# light_120mm_v1_0.net
KiCad netlist of a schematic drawn in EAGLE
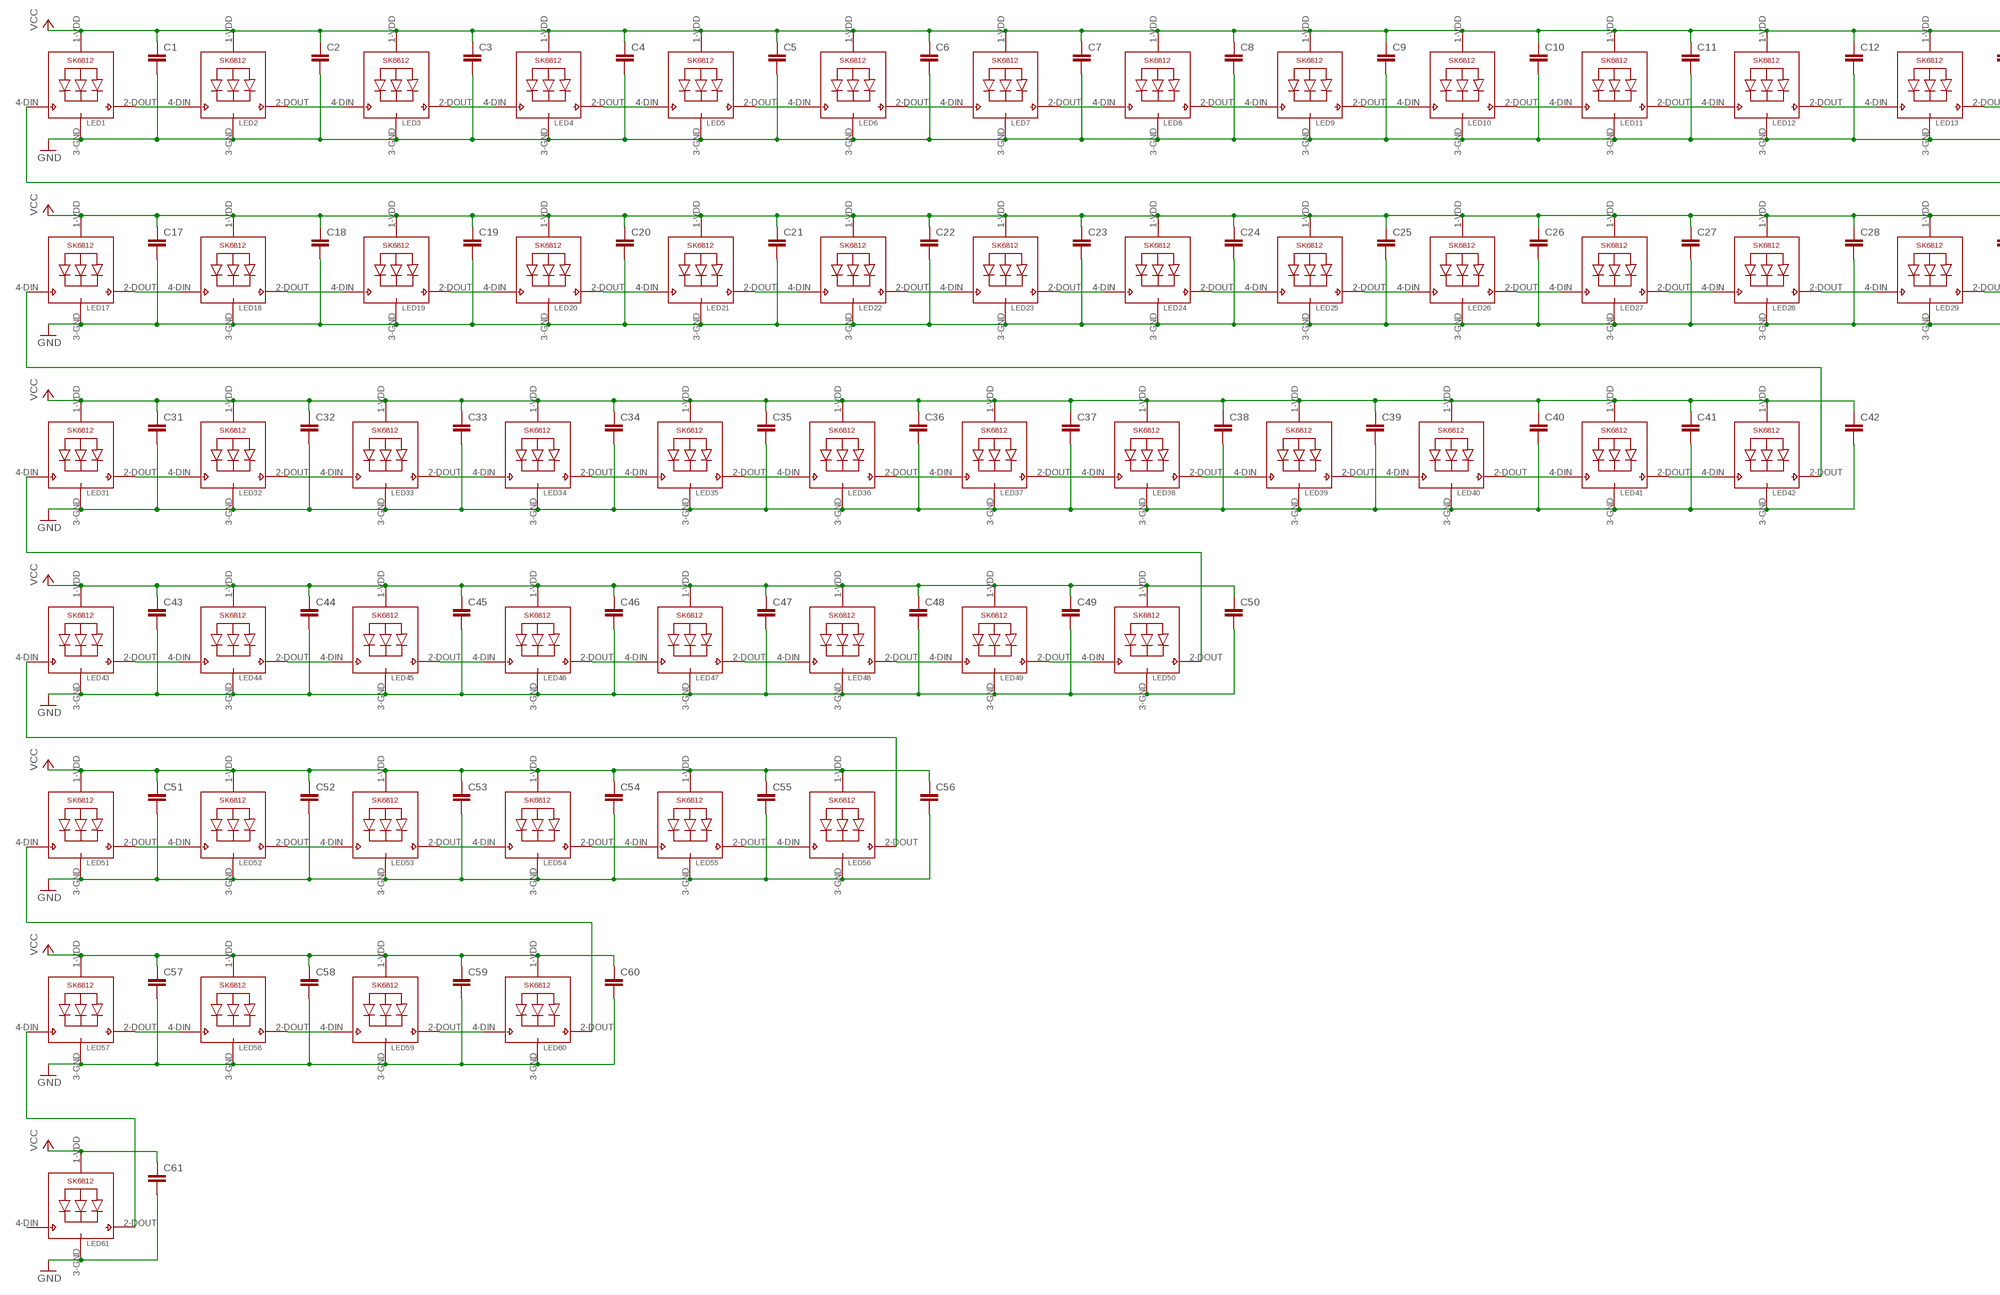
[diagram p0: schematic, sheet 1, part 1 of 2]
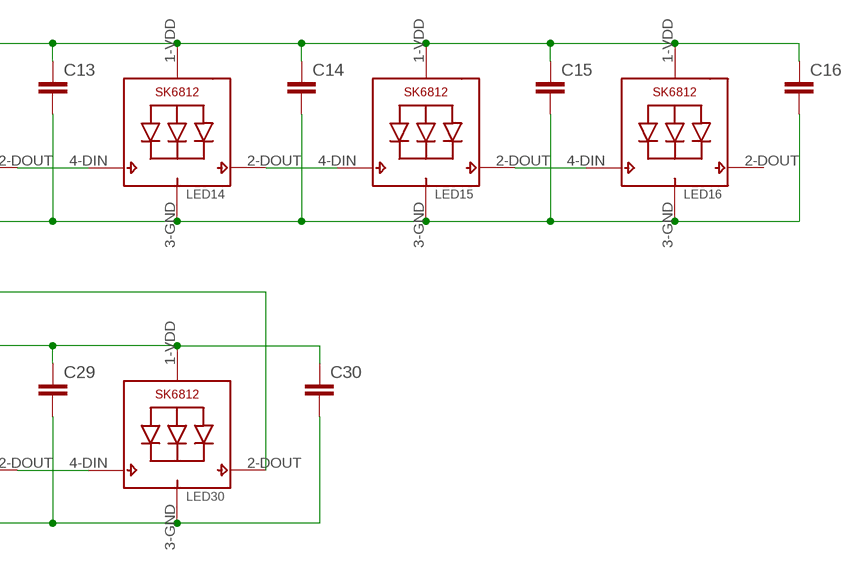
[diagram p1: schematic, sheet 1, part 2 of 2]

(export (version "E")
  (design (tool "Eeschema 10.0.6"))
  (components
    (comp (ref "C1")
      (value "C-EUC0805")
      (footprint "eagle-import:C0805")
      (libsource (lib "eagle-import") (part "C-EUC0805"))
    )
    (comp (ref "C2")
      (value "C-EUC0805")
      (footprint "eagle-import:C0805")
      (libsource (lib "eagle-import") (part "C-EUC0805"))
    )
    (comp (ref "C3")
      (value "C-EUC0805")
      (footprint "eagle-import:C0805")
      (libsource (lib "eagle-import") (part "C-EUC0805"))
    )
    (comp (ref "C4")
      (value "C-EUC0805")
      (footprint "eagle-import:C0805")
      (libsource (lib "eagle-import") (part "C-EUC0805"))
    )
    (comp (ref "C5")
      (value "C-EUC0805")
      (footprint "eagle-import:C0805")
      (libsource (lib "eagle-import") (part "C-EUC0805"))
    )
    (comp (ref "C6")
      (value "C-EUC0805")
      (footprint "eagle-import:C0805")
      (libsource (lib "eagle-import") (part "C-EUC0805"))
    )
    (comp (ref "C7")
      (value "C-EUC0805")
      (footprint "eagle-import:C0805")
      (libsource (lib "eagle-import") (part "C-EUC0805"))
    )
    (comp (ref "C8")
      (value "C-EUC0805")
      (footprint "eagle-import:C0805")
      (libsource (lib "eagle-import") (part "C-EUC0805"))
    )
    (comp (ref "C9")
      (value "C-EUC0805")
      (footprint "eagle-import:C0805")
      (libsource (lib "eagle-import") (part "C-EUC0805"))
    )
    (comp (ref "C10")
      (value "C-EUC0805")
      (footprint "eagle-import:C0805")
      (libsource (lib "eagle-import") (part "C-EUC0805"))
    )
    (comp (ref "C11")
      (value "C-EUC0805")
      (footprint "eagle-import:C0805")
      (libsource (lib "eagle-import") (part "C-EUC0805"))
    )
    (comp (ref "C12")
      (value "C-EUC0805")
      (footprint "eagle-import:C0805")
      (libsource (lib "eagle-import") (part "C-EUC0805"))
    )
    (comp (ref "C13")
      (value "C-EUC0805")
      (footprint "eagle-import:C0805")
      (libsource (lib "eagle-import") (part "C-EUC0805"))
    )
    (comp (ref "C14")
      (value "C-EUC0805")
      (footprint "eagle-import:C0805")
      (libsource (lib "eagle-import") (part "C-EUC0805"))
    )
    (comp (ref "C15")
      (value "C-EUC0805")
      (footprint "eagle-import:C0805")
      (libsource (lib "eagle-import") (part "C-EUC0805"))
    )
    (comp (ref "C16")
      (value "C-EUC0805")
      (footprint "eagle-import:C0805")
      (libsource (lib "eagle-import") (part "C-EUC0805"))
    )
    (comp (ref "C17")
      (value "C-EUC0805")
      (footprint "eagle-import:C0805")
      (libsource (lib "eagle-import") (part "C-EUC0805"))
    )
    (comp (ref "C18")
      (value "C-EUC0805")
      (footprint "eagle-import:C0805")
      (libsource (lib "eagle-import") (part "C-EUC0805"))
    )
    (comp (ref "C19")
      (value "C-EUC0805")
      (footprint "eagle-import:C0805")
      (libsource (lib "eagle-import") (part "C-EUC0805"))
    )
    (comp (ref "C20")
      (value "C-EUC0805")
      (footprint "eagle-import:C0805")
      (libsource (lib "eagle-import") (part "C-EUC0805"))
    )
    (comp (ref "C21")
      (value "C-EUC0805")
      (footprint "eagle-import:C0805")
      (libsource (lib "eagle-import") (part "C-EUC0805"))
    )
    (comp (ref "C22")
      (value "C-EUC0805")
      (footprint "eagle-import:C0805")
      (libsource (lib "eagle-import") (part "C-EUC0805"))
    )
    (comp (ref "C23")
      (value "C-EUC0805")
      (footprint "eagle-import:C0805")
      (libsource (lib "eagle-import") (part "C-EUC0805"))
    )
    (comp (ref "C24")
      (value "C-EUC0805")
      (footprint "eagle-import:C0805")
      (libsource (lib "eagle-import") (part "C-EUC0805"))
    )
    (comp (ref "C25")
      (value "C-EUC0805")
      (footprint "eagle-import:C0805")
      (libsource (lib "eagle-import") (part "C-EUC0805"))
    )
    (comp (ref "C26")
      (value "C-EUC0805")
      (footprint "eagle-import:C0805")
      (libsource (lib "eagle-import") (part "C-EUC0805"))
    )
    (comp (ref "C27")
      (value "C-EUC0805")
      (footprint "eagle-import:C0805")
      (libsource (lib "eagle-import") (part "C-EUC0805"))
    )
    (comp (ref "C28")
      (value "C-EUC0805")
      (footprint "eagle-import:C0805")
      (libsource (lib "eagle-import") (part "C-EUC0805"))
    )
    (comp (ref "C29")
      (value "C-EUC0805")
      (footprint "eagle-import:C0805")
      (libsource (lib "eagle-import") (part "C-EUC0805"))
    )
    (comp (ref "C30")
      (value "C-EUC0805")
      (footprint "eagle-import:C0805")
      (libsource (lib "eagle-import") (part "C-EUC0805"))
    )
    (comp (ref "C31")
      (value "C-EUC0805")
      (footprint "eagle-import:C0805")
      (libsource (lib "eagle-import") (part "C-EUC0805"))
    )
    (comp (ref "C32")
      (value "C-EUC0805")
      (footprint "eagle-import:C0805")
      (libsource (lib "eagle-import") (part "C-EUC0805"))
    )
    (comp (ref "C33")
      (value "C-EUC0805")
      (footprint "eagle-import:C0805")
      (libsource (lib "eagle-import") (part "C-EUC0805"))
    )
    (comp (ref "C34")
      (value "C-EUC0805")
      (footprint "eagle-import:C0805")
      (libsource (lib "eagle-import") (part "C-EUC0805"))
    )
    (comp (ref "C35")
      (value "C-EUC0805")
      (footprint "eagle-import:C0805")
      (libsource (lib "eagle-import") (part "C-EUC0805"))
    )
    (comp (ref "C36")
      (value "C-EUC0805")
      (footprint "eagle-import:C0805")
      (libsource (lib "eagle-import") (part "C-EUC0805"))
    )
    (comp (ref "C37")
      (value "C-EUC0805")
      (footprint "eagle-import:C0805")
      (libsource (lib "eagle-import") (part "C-EUC0805"))
    )
    (comp (ref "C38")
      (value "C-EUC0805")
      (footprint "eagle-import:C0805")
      (libsource (lib "eagle-import") (part "C-EUC0805"))
    )
    (comp (ref "C39")
      (value "C-EUC0805")
      (footprint "eagle-import:C0805")
      (libsource (lib "eagle-import") (part "C-EUC0805"))
    )
    (comp (ref "C40")
      (value "C-EUC0805")
      (footprint "eagle-import:C0805")
      (libsource (lib "eagle-import") (part "C-EUC0805"))
    )
    (comp (ref "C41")
      (value "C-EUC0805")
      (footprint "eagle-import:C0805")
      (libsource (lib "eagle-import") (part "C-EUC0805"))
    )
    (comp (ref "C42")
      (value "C-EUC0805")
      (footprint "eagle-import:C0805")
      (libsource (lib "eagle-import") (part "C-EUC0805"))
    )
    (comp (ref "C43")
      (value "C-EUC0805")
      (footprint "eagle-import:C0805")
      (libsource (lib "eagle-import") (part "C-EUC0805"))
    )
    (comp (ref "C44")
      (value "C-EUC0805")
      (footprint "eagle-import:C0805")
      (libsource (lib "eagle-import") (part "C-EUC0805"))
    )
    (comp (ref "C45")
      (value "C-EUC0805")
      (footprint "eagle-import:C0805")
      (libsource (lib "eagle-import") (part "C-EUC0805"))
    )
    (comp (ref "C46")
      (value "C-EUC0805")
      (footprint "eagle-import:C0805")
      (libsource (lib "eagle-import") (part "C-EUC0805"))
    )
    (comp (ref "C47")
      (value "C-EUC0805")
      (footprint "eagle-import:C0805")
      (libsource (lib "eagle-import") (part "C-EUC0805"))
    )
    (comp (ref "C48")
      (value "C-EUC0805")
      (footprint "eagle-import:C0805")
      (libsource (lib "eagle-import") (part "C-EUC0805"))
    )
    (comp (ref "C49")
      (value "C-EUC0805")
      (footprint "eagle-import:C0805")
      (libsource (lib "eagle-import") (part "C-EUC0805"))
    )
    (comp (ref "C50")
      (value "C-EUC0805")
      (footprint "eagle-import:C0805")
      (libsource (lib "eagle-import") (part "C-EUC0805"))
    )
    (comp (ref "C51")
      (value "C-EUC0805")
      (footprint "eagle-import:C0805")
      (libsource (lib "eagle-import") (part "C-EUC0805"))
    )
    (comp (ref "C52")
      (value "C-EUC0805")
      (footprint "eagle-import:C0805")
      (libsource (lib "eagle-import") (part "C-EUC0805"))
    )
    (comp (ref "C53")
      (value "C-EUC0805")
      (footprint "eagle-import:C0805")
      (libsource (lib "eagle-import") (part "C-EUC0805"))
    )
    (comp (ref "C54")
      (value "C-EUC0805")
      (footprint "eagle-import:C0805")
      (libsource (lib "eagle-import") (part "C-EUC0805"))
    )
    (comp (ref "C55")
      (value "C-EUC0805")
      (footprint "eagle-import:C0805")
      (libsource (lib "eagle-import") (part "C-EUC0805"))
    )
    (comp (ref "C56")
      (value "C-EUC0805")
      (footprint "eagle-import:C0805")
      (libsource (lib "eagle-import") (part "C-EUC0805"))
    )
    (comp (ref "C57")
      (value "C-EUC0805")
      (footprint "eagle-import:C0805")
      (libsource (lib "eagle-import") (part "C-EUC0805"))
    )
    (comp (ref "C58")
      (value "C-EUC0805")
      (footprint "eagle-import:C0805")
      (libsource (lib "eagle-import") (part "C-EUC0805"))
    )
    (comp (ref "C59")
      (value "C-EUC0805")
      (footprint "eagle-import:C0805")
      (libsource (lib "eagle-import") (part "C-EUC0805"))
    )
    (comp (ref "C60")
      (value "C-EUC0805")
      (footprint "eagle-import:C0805")
      (libsource (lib "eagle-import") (part "C-EUC0805"))
    )
    (comp (ref "C61")
      (value "C-EUC0805")
      (footprint "eagle-import:C0805")
      (libsource (lib "eagle-import") (part "C-EUC0805"))
    )
    (comp (ref "LED1")
      (value "SK6812_5050W")
      (footprint "eagle-import:LED5050_W")
      (libsource (lib "eagle-import") (part "SK6812_5050W"))
    )
    (comp (ref "LED2")
      (value "SK6812_5050W")
      (footprint "eagle-import:LED5050_W")
      (libsource (lib "eagle-import") (part "SK6812_5050W"))
    )
    (comp (ref "LED3")
      (value "SK6812_5050W")
      (footprint "eagle-import:LED5050_W")
      (libsource (lib "eagle-import") (part "SK6812_5050W"))
    )
    (comp (ref "LED4")
      (value "SK6812_5050W")
      (footprint "eagle-import:LED5050_W")
      (libsource (lib "eagle-import") (part "SK6812_5050W"))
    )
    (comp (ref "LED5")
      (value "SK6812_5050W")
      (footprint "eagle-import:LED5050_W")
      (libsource (lib "eagle-import") (part "SK6812_5050W"))
    )
    (comp (ref "LED6")
      (value "SK6812_5050W")
      (footprint "eagle-import:LED5050_W")
      (libsource (lib "eagle-import") (part "SK6812_5050W"))
    )
    (comp (ref "LED7")
      (value "SK6812_5050W")
      (footprint "eagle-import:LED5050_W")
      (libsource (lib "eagle-import") (part "SK6812_5050W"))
    )
    (comp (ref "LED8")
      (value "SK6812_5050W")
      (footprint "eagle-import:LED5050_W")
      (libsource (lib "eagle-import") (part "SK6812_5050W"))
    )
    (comp (ref "LED9")
      (value "SK6812_5050W")
      (footprint "eagle-import:LED5050_W")
      (libsource (lib "eagle-import") (part "SK6812_5050W"))
    )
    (comp (ref "LED10")
      (value "SK6812_5050W")
      (footprint "eagle-import:LED5050_W")
      (libsource (lib "eagle-import") (part "SK6812_5050W"))
    )
    (comp (ref "LED11")
      (value "SK6812_5050W")
      (footprint "eagle-import:LED5050_W")
      (libsource (lib "eagle-import") (part "SK6812_5050W"))
    )
    (comp (ref "LED12")
      (value "SK6812_5050W")
      (footprint "eagle-import:LED5050_W")
      (libsource (lib "eagle-import") (part "SK6812_5050W"))
    )
    (comp (ref "LED13")
      (value "SK6812_5050W")
      (footprint "eagle-import:LED5050_W")
      (libsource (lib "eagle-import") (part "SK6812_5050W"))
    )
    (comp (ref "LED14")
      (value "SK6812_5050W")
      (footprint "eagle-import:LED5050_W")
      (libsource (lib "eagle-import") (part "SK6812_5050W"))
    )
    (comp (ref "LED15")
      (value "SK6812_5050W")
      (footprint "eagle-import:LED5050_W")
      (libsource (lib "eagle-import") (part "SK6812_5050W"))
    )
    (comp (ref "LED16")
      (value "SK6812_5050W")
      (footprint "eagle-import:LED5050_W")
      (libsource (lib "eagle-import") (part "SK6812_5050W"))
    )
    (comp (ref "LED17")
      (value "SK6812_5050W")
      (footprint "eagle-import:LED5050_W")
      (libsource (lib "eagle-import") (part "SK6812_5050W"))
    )
    (comp (ref "LED18")
      (value "SK6812_5050W")
      (footprint "eagle-import:LED5050_W")
      (libsource (lib "eagle-import") (part "SK6812_5050W"))
    )
    (comp (ref "LED19")
      (value "SK6812_5050W")
      (footprint "eagle-import:LED5050_W")
      (libsource (lib "eagle-import") (part "SK6812_5050W"))
    )
    (comp (ref "LED20")
      (value "SK6812_5050W")
      (footprint "eagle-import:LED5050_W")
      (libsource (lib "eagle-import") (part "SK6812_5050W"))
    )
    (comp (ref "LED21")
      (value "SK6812_5050W")
      (footprint "eagle-import:LED5050_W")
      (libsource (lib "eagle-import") (part "SK6812_5050W"))
    )
    (comp (ref "LED22")
      (value "SK6812_5050W")
      (footprint "eagle-import:LED5050_W")
      (libsource (lib "eagle-import") (part "SK6812_5050W"))
    )
    (comp (ref "LED23")
      (value "SK6812_5050W")
      (footprint "eagle-import:LED5050_W")
      (libsource (lib "eagle-import") (part "SK6812_5050W"))
    )
    (comp (ref "LED24")
      (value "SK6812_5050W")
      (footprint "eagle-import:LED5050_W")
      (libsource (lib "eagle-import") (part "SK6812_5050W"))
    )
    (comp (ref "LED25")
      (value "SK6812_5050W")
      (footprint "eagle-import:LED5050_W")
      (libsource (lib "eagle-import") (part "SK6812_5050W"))
    )
    (comp (ref "LED26")
      (value "SK6812_5050W")
      (footprint "eagle-import:LED5050_W")
      (libsource (lib "eagle-import") (part "SK6812_5050W"))
    )
    (comp (ref "LED27")
      (value "SK6812_5050W")
      (footprint "eagle-import:LED5050_W")
      (libsource (lib "eagle-import") (part "SK6812_5050W"))
    )
    (comp (ref "LED28")
      (value "SK6812_5050W")
      (footprint "eagle-import:LED5050_W")
      (libsource (lib "eagle-import") (part "SK6812_5050W"))
    )
    (comp (ref "LED29")
      (value "SK6812_5050W")
      (footprint "eagle-import:LED5050_W")
      (libsource (lib "eagle-import") (part "SK6812_5050W"))
    )
    (comp (ref "LED30")
      (value "SK6812_5050W")
      (footprint "eagle-import:LED5050_W")
      (libsource (lib "eagle-import") (part "SK6812_5050W"))
    )
    (comp (ref "LED31")
      (value "SK6812_5050W")
      (footprint "eagle-import:LED5050_W")
      (libsource (lib "eagle-import") (part "SK6812_5050W"))
    )
    (comp (ref "LED32")
      (value "SK6812_5050W")
      (footprint "eagle-import:LED5050_W")
      (libsource (lib "eagle-import") (part "SK6812_5050W"))
    )
    (comp (ref "LED33")
      (value "SK6812_5050W")
      (footprint "eagle-import:LED5050_W")
      (libsource (lib "eagle-import") (part "SK6812_5050W"))
    )
    (comp (ref "LED34")
      (value "SK6812_5050W")
      (footprint "eagle-import:LED5050_W")
      (libsource (lib "eagle-import") (part "SK6812_5050W"))
    )
    (comp (ref "LED35")
      (value "SK6812_5050W")
      (footprint "eagle-import:LED5050_W")
      (libsource (lib "eagle-import") (part "SK6812_5050W"))
    )
    (comp (ref "LED36")
      (value "SK6812_5050W")
      (footprint "eagle-import:LED5050_W")
      (libsource (lib "eagle-import") (part "SK6812_5050W"))
    )
    (comp (ref "LED37")
      (value "SK6812_5050W")
      (footprint "eagle-import:LED5050_W")
      (libsource (lib "eagle-import") (part "SK6812_5050W"))
    )
    (comp (ref "LED38")
      (value "SK6812_5050W")
      (footprint "eagle-import:LED5050_W")
      (libsource (lib "eagle-import") (part "SK6812_5050W"))
    )
    (comp (ref "LED39")
      (value "SK6812_5050W")
      (footprint "eagle-import:LED5050_W")
      (libsource (lib "eagle-import") (part "SK6812_5050W"))
    )
    (comp (ref "LED40")
      (value "SK6812_5050W")
      (footprint "eagle-import:LED5050_W")
      (libsource (lib "eagle-import") (part "SK6812_5050W"))
    )
    (comp (ref "LED41")
      (value "SK6812_5050W")
      (footprint "eagle-import:LED5050_W")
      (libsource (lib "eagle-import") (part "SK6812_5050W"))
    )
    (comp (ref "LED42")
      (value "SK6812_5050W")
      (footprint "eagle-import:LED5050_W")
      (libsource (lib "eagle-import") (part "SK6812_5050W"))
    )
    (comp (ref "LED43")
      (value "SK6812_5050W")
      (footprint "eagle-import:LED5050_W")
      (libsource (lib "eagle-import") (part "SK6812_5050W"))
    )
    (comp (ref "LED44")
      (value "SK6812_5050W")
      (footprint "eagle-import:LED5050_W")
      (libsource (lib "eagle-import") (part "SK6812_5050W"))
    )
    (comp (ref "LED45")
      (value "SK6812_5050W")
      (footprint "eagle-import:LED5050_W")
      (libsource (lib "eagle-import") (part "SK6812_5050W"))
    )
    (comp (ref "LED46")
      (value "SK6812_5050W")
      (footprint "eagle-import:LED5050_W")
      (libsource (lib "eagle-import") (part "SK6812_5050W"))
    )
    (comp (ref "LED47")
      (value "SK6812_5050W")
      (footprint "eagle-import:LED5050_W")
      (libsource (lib "eagle-import") (part "SK6812_5050W"))
    )
    (comp (ref "LED48")
      (value "SK6812_5050W")
      (footprint "eagle-import:LED5050_W")
      (libsource (lib "eagle-import") (part "SK6812_5050W"))
    )
    (comp (ref "LED49")
      (value "SK6812_5050W")
      (footprint "eagle-import:LED5050_W")
      (libsource (lib "eagle-import") (part "SK6812_5050W"))
    )
    (comp (ref "LED50")
      (value "SK6812_5050W")
      (footprint "eagle-import:LED5050_W")
      (libsource (lib "eagle-import") (part "SK6812_5050W"))
    )
    (comp (ref "LED51")
      (value "SK6812_5050W")
      (footprint "eagle-import:LED5050_W")
      (libsource (lib "eagle-import") (part "SK6812_5050W"))
    )
    (comp (ref "LED52")
      (value "SK6812_5050W")
      (footprint "eagle-import:LED5050_W")
      (libsource (lib "eagle-import") (part "SK6812_5050W"))
    )
    (comp (ref "LED53")
      (value "SK6812_5050W")
      (footprint "eagle-import:LED5050_W")
      (libsource (lib "eagle-import") (part "SK6812_5050W"))
    )
    (comp (ref "LED54")
      (value "SK6812_5050W")
      (footprint "eagle-import:LED5050_W")
      (libsource (lib "eagle-import") (part "SK6812_5050W"))
    )
    (comp (ref "LED55")
      (value "SK6812_5050W")
      (footprint "eagle-import:LED5050_W")
      (libsource (lib "eagle-import") (part "SK6812_5050W"))
    )
    (comp (ref "LED56")
      (value "SK6812_5050W")
      (footprint "eagle-import:LED5050_W")
      (libsource (lib "eagle-import") (part "SK6812_5050W"))
    )
    (comp (ref "LED57")
      (value "SK6812_5050W")
      (footprint "eagle-import:LED5050_W")
      (libsource (lib "eagle-import") (part "SK6812_5050W"))
    )
    (comp (ref "LED58")
      (value "SK6812_5050W")
      (footprint "eagle-import:LED5050_W")
      (libsource (lib "eagle-import") (part "SK6812_5050W"))
    )
    (comp (ref "LED59")
      (value "SK6812_5050W")
      (footprint "eagle-import:LED5050_W")
      (libsource (lib "eagle-import") (part "SK6812_5050W"))
    )
    (comp (ref "LED60")
      (value "SK6812_5050W")
      (footprint "eagle-import:LED5050_W")
      (libsource (lib "eagle-import") (part "SK6812_5050W"))
    )
    (comp (ref "LED61")
      (value "SK6812_5050W")
      (footprint "eagle-import:LED5050_W")
      (libsource (lib "eagle-import") (part "SK6812_5050W"))
    )
  )
  (nets
    (net (code "1") (name "GND") (class "Default")
      (node (ref "C1") (pin "2") (pinfunction "2_2") (pintype "passive"))
      (node (ref "C10") (pin "2") (pinfunction "2_2") (pintype "passive"))
      (node (ref "C11") (pin "2") (pinfunction "2_2") (pintype "passive"))
      (node (ref "C12") (pin "2") (pinfunction "2_2") (pintype "passive"))
      (node (ref "C13") (pin "2") (pinfunction "2_2") (pintype "passive"))
      (node (ref "C14") (pin "2") (pinfunction "2_2") (pintype "passive"))
      (node (ref "C15") (pin "2") (pinfunction "2_2") (pintype "passive"))
      (node (ref "C16") (pin "2") (pinfunction "2_2") (pintype "passive"))
      (node (ref "C17") (pin "2") (pinfunction "2_2") (pintype "passive"))
      (node (ref "C18") (pin "2") (pinfunction "2_2") (pintype "passive"))
      (node (ref "C19") (pin "2") (pinfunction "2_2") (pintype "passive"))
      (node (ref "C2") (pin "2") (pinfunction "2_2") (pintype "passive"))
      (node (ref "C20") (pin "2") (pinfunction "2_2") (pintype "passive"))
      (node (ref "C21") (pin "2") (pinfunction "2_2") (pintype "passive"))
      (node (ref "C22") (pin "2") (pinfunction "2_2") (pintype "passive"))
      (node (ref "C23") (pin "2") (pinfunction "2_2") (pintype "passive"))
      (node (ref "C24") (pin "2") (pinfunction "2_2") (pintype "passive"))
      (node (ref "C25") (pin "2") (pinfunction "2_2") (pintype "passive"))
      (node (ref "C26") (pin "2") (pinfunction "2_2") (pintype "passive"))
      (node (ref "C27") (pin "2") (pinfunction "2_2") (pintype "passive"))
      (node (ref "C28") (pin "2") (pinfunction "2_2") (pintype "passive"))
      (node (ref "C29") (pin "2") (pinfunction "2_2") (pintype "passive"))
      (node (ref "C3") (pin "2") (pinfunction "2_2") (pintype "passive"))
      (node (ref "C30") (pin "2") (pinfunction "2_2") (pintype "passive"))
      (node (ref "C31") (pin "2") (pinfunction "2_2") (pintype "passive"))
      (node (ref "C32") (pin "2") (pinfunction "2_2") (pintype "passive"))
      (node (ref "C33") (pin "2") (pinfunction "2_2") (pintype "passive"))
      (node (ref "C34") (pin "2") (pinfunction "2_2") (pintype "passive"))
      (node (ref "C35") (pin "2") (pinfunction "2_2") (pintype "passive"))
      (node (ref "C36") (pin "2") (pinfunction "2_2") (pintype "passive"))
      (node (ref "C37") (pin "2") (pinfunction "2_2") (pintype "passive"))
      (node (ref "C38") (pin "2") (pinfunction "2_2") (pintype "passive"))
      (node (ref "C39") (pin "2") (pinfunction "2_2") (pintype "passive"))
      (node (ref "C4") (pin "2") (pinfunction "2_2") (pintype "passive"))
      (node (ref "C40") (pin "2") (pinfunction "2_2") (pintype "passive"))
      (node (ref "C41") (pin "2") (pinfunction "2_2") (pintype "passive"))
      (node (ref "C42") (pin "2") (pinfunction "2_2") (pintype "passive"))
      (node (ref "C43") (pin "2") (pinfunction "2_2") (pintype "passive"))
      (node (ref "C44") (pin "2") (pinfunction "2_2") (pintype "passive"))
      (node (ref "C45") (pin "2") (pinfunction "2_2") (pintype "passive"))
      (node (ref "C46") (pin "2") (pinfunction "2_2") (pintype "passive"))
      (node (ref "C47") (pin "2") (pinfunction "2_2") (pintype "passive"))
      (node (ref "C48") (pin "2") (pinfunction "2_2") (pintype "passive"))
      (node (ref "C49") (pin "2") (pinfunction "2_2") (pintype "passive"))
      (node (ref "C5") (pin "2") (pinfunction "2_2") (pintype "passive"))
      (node (ref "C50") (pin "2") (pinfunction "2_2") (pintype "passive"))
      (node (ref "C51") (pin "2") (pinfunction "2_2") (pintype "passive"))
      (node (ref "C52") (pin "2") (pinfunction "2_2") (pintype "passive"))
      (node (ref "C53") (pin "2") (pinfunction "2_2") (pintype "passive"))
      (node (ref "C54") (pin "2") (pinfunction "2_2") (pintype "passive"))
      (node (ref "C55") (pin "2") (pinfunction "2_2") (pintype "passive"))
      (node (ref "C56") (pin "2") (pinfunction "2_2") (pintype "passive"))
      (node (ref "C57") (pin "2") (pinfunction "2_2") (pintype "passive"))
      (node (ref "C58") (pin "2") (pinfunction "2_2") (pintype "passive"))
      (node (ref "C59") (pin "2") (pinfunction "2_2") (pintype "passive"))
      (node (ref "C6") (pin "2") (pinfunction "2_2") (pintype "passive"))
      (node (ref "C60") (pin "2") (pinfunction "2_2") (pintype "passive"))
      (node (ref "C61") (pin "2") (pinfunction "2_2") (pintype "passive"))
      (node (ref "C7") (pin "2") (pinfunction "2_2") (pintype "passive"))
      (node (ref "C8") (pin "2") (pinfunction "2_2") (pintype "passive"))
      (node (ref "C9") (pin "2") (pinfunction "2_2") (pintype "passive"))
      (node (ref "LED1") (pin "3-GND") (pinfunction "GND_3-GND") (pintype "power_in"))
      (node (ref "LED10") (pin "3-GND") (pinfunction "GND_3-GND") (pintype "power_in"))
      (node (ref "LED11") (pin "3-GND") (pinfunction "GND_3-GND") (pintype "power_in"))
      (node (ref "LED12") (pin "3-GND") (pinfunction "GND_3-GND") (pintype "power_in"))
      (node (ref "LED13") (pin "3-GND") (pinfunction "GND_3-GND") (pintype "power_in"))
      (node (ref "LED14") (pin "3-GND") (pinfunction "GND_3-GND") (pintype "power_in"))
      (node (ref "LED15") (pin "3-GND") (pinfunction "GND_3-GND") (pintype "power_in"))
      (node (ref "LED16") (pin "3-GND") (pinfunction "GND_3-GND") (pintype "power_in"))
      (node (ref "LED17") (pin "3-GND") (pinfunction "GND_3-GND") (pintype "power_in"))
      (node (ref "LED18") (pin "3-GND") (pinfunction "GND_3-GND") (pintype "power_in"))
      (node (ref "LED19") (pin "3-GND") (pinfunction "GND_3-GND") (pintype "power_in"))
      (node (ref "LED2") (pin "3-GND") (pinfunction "GND_3-GND") (pintype "power_in"))
      (node (ref "LED20") (pin "3-GND") (pinfunction "GND_3-GND") (pintype "power_in"))
      (node (ref "LED21") (pin "3-GND") (pinfunction "GND_3-GND") (pintype "power_in"))
      (node (ref "LED22") (pin "3-GND") (pinfunction "GND_3-GND") (pintype "power_in"))
      (node (ref "LED23") (pin "3-GND") (pinfunction "GND_3-GND") (pintype "power_in"))
      (node (ref "LED24") (pin "3-GND") (pinfunction "GND_3-GND") (pintype "power_in"))
      (node (ref "LED25") (pin "3-GND") (pinfunction "GND_3-GND") (pintype "power_in"))
      (node (ref "LED26") (pin "3-GND") (pinfunction "GND_3-GND") (pintype "power_in"))
      (node (ref "LED27") (pin "3-GND") (pinfunction "GND_3-GND") (pintype "power_in"))
      (node (ref "LED28") (pin "3-GND") (pinfunction "GND_3-GND") (pintype "power_in"))
      (node (ref "LED29") (pin "3-GND") (pinfunction "GND_3-GND") (pintype "power_in"))
      (node (ref "LED3") (pin "3-GND") (pinfunction "GND_3-GND") (pintype "power_in"))
      (node (ref "LED30") (pin "3-GND") (pinfunction "GND_3-GND") (pintype "power_in"))
      (node (ref "LED31") (pin "3-GND") (pinfunction "GND_3-GND") (pintype "power_in"))
      (node (ref "LED32") (pin "3-GND") (pinfunction "GND_3-GND") (pintype "power_in"))
      (node (ref "LED33") (pin "3-GND") (pinfunction "GND_3-GND") (pintype "power_in"))
      (node (ref "LED34") (pin "3-GND") (pinfunction "GND_3-GND") (pintype "power_in"))
      (node (ref "LED35") (pin "3-GND") (pinfunction "GND_3-GND") (pintype "power_in"))
      (node (ref "LED36") (pin "3-GND") (pinfunction "GND_3-GND") (pintype "power_in"))
      (node (ref "LED37") (pin "3-GND") (pinfunction "GND_3-GND") (pintype "power_in"))
      (node (ref "LED38") (pin "3-GND") (pinfunction "GND_3-GND") (pintype "power_in"))
      (node (ref "LED39") (pin "3-GND") (pinfunction "GND_3-GND") (pintype "power_in"))
      (node (ref "LED4") (pin "3-GND") (pinfunction "GND_3-GND") (pintype "power_in"))
      (node (ref "LED40") (pin "3-GND") (pinfunction "GND_3-GND") (pintype "power_in"))
      (node (ref "LED41") (pin "3-GND") (pinfunction "GND_3-GND") (pintype "power_in"))
      (node (ref "LED42") (pin "3-GND") (pinfunction "GND_3-GND") (pintype "power_in"))
      (node (ref "LED43") (pin "3-GND") (pinfunction "GND_3-GND") (pintype "power_in"))
      (node (ref "LED44") (pin "3-GND") (pinfunction "GND_3-GND") (pintype "power_in"))
      (node (ref "LED45") (pin "3-GND") (pinfunction "GND_3-GND") (pintype "power_in"))
      (node (ref "LED46") (pin "3-GND") (pinfunction "GND_3-GND") (pintype "power_in"))
      (node (ref "LED47") (pin "3-GND") (pinfunction "GND_3-GND") (pintype "power_in"))
      (node (ref "LED48") (pin "3-GND") (pinfunction "GND_3-GND") (pintype "power_in"))
      (node (ref "LED49") (pin "3-GND") (pinfunction "GND_3-GND") (pintype "power_in"))
      (node (ref "LED5") (pin "3-GND") (pinfunction "GND_3-GND") (pintype "power_in"))
      (node (ref "LED50") (pin "3-GND") (pinfunction "GND_3-GND") (pintype "power_in"))
      (node (ref "LED51") (pin "3-GND") (pinfunction "GND_3-GND") (pintype "power_in"))
      (node (ref "LED52") (pin "3-GND") (pinfunction "GND_3-GND") (pintype "power_in"))
      (node (ref "LED53") (pin "3-GND") (pinfunction "GND_3-GND") (pintype "power_in"))
      (node (ref "LED54") (pin "3-GND") (pinfunction "GND_3-GND") (pintype "power_in"))
      (node (ref "LED55") (pin "3-GND") (pinfunction "GND_3-GND") (pintype "power_in"))
      (node (ref "LED56") (pin "3-GND") (pinfunction "GND_3-GND") (pintype "power_in"))
      (node (ref "LED57") (pin "3-GND") (pinfunction "GND_3-GND") (pintype "power_in"))
      (node (ref "LED58") (pin "3-GND") (pinfunction "GND_3-GND") (pintype "power_in"))
      (node (ref "LED59") (pin "3-GND") (pinfunction "GND_3-GND") (pintype "power_in"))
      (node (ref "LED6") (pin "3-GND") (pinfunction "GND_3-GND") (pintype "power_in"))
      (node (ref "LED60") (pin "3-GND") (pinfunction "GND_3-GND") (pintype "power_in"))
      (node (ref "LED61") (pin "3-GND") (pinfunction "GND_3-GND") (pintype "power_in"))
      (node (ref "LED7") (pin "3-GND") (pinfunction "GND_3-GND") (pintype "power_in"))
      (node (ref "LED8") (pin "3-GND") (pinfunction "GND_3-GND") (pintype "power_in"))
      (node (ref "LED9") (pin "3-GND") (pinfunction "GND_3-GND") (pintype "power_in"))
    )
    (net (code "2") (name "Net-(LED1-DI)") (class "Default")
      (node (ref "LED1") (pin "4-DIN") (pinfunction "DI_4-DIN") (pintype "input"))
      (node (ref "LED30") (pin "2-DOUT") (pinfunction "DO_2-DOUT") (pintype "output"))
    )
    (net (code "3") (name "Net-(LED1-DO)") (class "Default")
      (node (ref "LED1") (pin "2-DOUT") (pinfunction "DO_2-DOUT") (pintype "output"))
      (node (ref "LED2") (pin "4-DIN") (pinfunction "DI_4-DIN") (pintype "input"))
    )
    (net (code "4") (name "Net-(LED2-DO)") (class "Default")
      (node (ref "LED2") (pin "2-DOUT") (pinfunction "DO_2-DOUT") (pintype "output"))
      (node (ref "LED3") (pin "4-DIN") (pinfunction "DI_4-DIN") (pintype "input"))
    )
    (net (code "5") (name "Net-(LED3-DO)") (class "Default")
      (node (ref "LED3") (pin "2-DOUT") (pinfunction "DO_2-DOUT") (pintype "output"))
      (node (ref "LED4") (pin "4-DIN") (pinfunction "DI_4-DIN") (pintype "input"))
    )
    (net (code "6") (name "Net-(LED4-DO)") (class "Default")
      (node (ref "LED4") (pin "2-DOUT") (pinfunction "DO_2-DOUT") (pintype "output"))
      (node (ref "LED5") (pin "4-DIN") (pinfunction "DI_4-DIN") (pintype "input"))
    )
    (net (code "7") (name "Net-(LED5-DO)") (class "Default")
      (node (ref "LED5") (pin "2-DOUT") (pinfunction "DO_2-DOUT") (pintype "output"))
      (node (ref "LED6") (pin "4-DIN") (pinfunction "DI_4-DIN") (pintype "input"))
    )
    (net (code "8") (name "Net-(LED6-DO)") (class "Default")
      (node (ref "LED6") (pin "2-DOUT") (pinfunction "DO_2-DOUT") (pintype "output"))
      (node (ref "LED7") (pin "4-DIN") (pinfunction "DI_4-DIN") (pintype "input"))
    )
    (net (code "9") (name "Net-(LED7-DO)") (class "Default")
      (node (ref "LED7") (pin "2-DOUT") (pinfunction "DO_2-DOUT") (pintype "output"))
      (node (ref "LED8") (pin "4-DIN") (pinfunction "DI_4-DIN") (pintype "input"))
    )
    (net (code "10") (name "Net-(LED8-DO)") (class "Default")
      (node (ref "LED8") (pin "2-DOUT") (pinfunction "DO_2-DOUT") (pintype "output"))
      (node (ref "LED9") (pin "4-DIN") (pinfunction "DI_4-DIN") (pintype "input"))
    )
    (net (code "11") (name "Net-(LED10-DI)") (class "Default")
      (node (ref "LED10") (pin "4-DIN") (pinfunction "DI_4-DIN") (pintype "input"))
      (node (ref "LED9") (pin "2-DOUT") (pinfunction "DO_2-DOUT") (pintype "output"))
    )
    (net (code "12") (name "Net-(LED10-DO)") (class "Default")
      (node (ref "LED10") (pin "2-DOUT") (pinfunction "DO_2-DOUT") (pintype "output"))
      (node (ref "LED11") (pin "4-DIN") (pinfunction "DI_4-DIN") (pintype "input"))
    )
    (net (code "13") (name "Net-(LED11-DO)") (class "Default")
      (node (ref "LED11") (pin "2-DOUT") (pinfunction "DO_2-DOUT") (pintype "output"))
      (node (ref "LED12") (pin "4-DIN") (pinfunction "DI_4-DIN") (pintype "input"))
    )
    (net (code "14") (name "Net-(LED12-DO)") (class "Default")
      (node (ref "LED12") (pin "2-DOUT") (pinfunction "DO_2-DOUT") (pintype "output"))
      (node (ref "LED13") (pin "4-DIN") (pinfunction "DI_4-DIN") (pintype "input"))
    )
    (net (code "15") (name "Net-(LED13-DO)") (class "Default")
      (node (ref "LED13") (pin "2-DOUT") (pinfunction "DO_2-DOUT") (pintype "output"))
      (node (ref "LED14") (pin "4-DIN") (pinfunction "DI_4-DIN") (pintype "input"))
    )
    (net (code "16") (name "Net-(LED14-DO)") (class "Default")
      (node (ref "LED14") (pin "2-DOUT") (pinfunction "DO_2-DOUT") (pintype "output"))
      (node (ref "LED15") (pin "4-DIN") (pinfunction "DI_4-DIN") (pintype "input"))
    )
    (net (code "17") (name "Net-(LED15-DO)") (class "Default")
      (node (ref "LED15") (pin "2-DOUT") (pinfunction "DO_2-DOUT") (pintype "output"))
      (node (ref "LED16") (pin "4-DIN") (pinfunction "DI_4-DIN") (pintype "input"))
    )
    (net (code "18") (name "Net-(LED17-DI)") (class "Default")
      (node (ref "LED17") (pin "4-DIN") (pinfunction "DI_4-DIN") (pintype "input"))
      (node (ref "LED42") (pin "2-DOUT") (pinfunction "DO_2-DOUT") (pintype "output"))
    )
    (net (code "19") (name "Net-(LED17-DO)") (class "Default")
      (node (ref "LED17") (pin "2-DOUT") (pinfunction "DO_2-DOUT") (pintype "output"))
      (node (ref "LED18") (pin "4-DIN") (pinfunction "DI_4-DIN") (pintype "input"))
    )
    (net (code "20") (name "Net-(LED18-DO)") (class "Default")
      (node (ref "LED18") (pin "2-DOUT") (pinfunction "DO_2-DOUT") (pintype "output"))
      (node (ref "LED19") (pin "4-DIN") (pinfunction "DI_4-DIN") (pintype "input"))
    )
    (net (code "21") (name "Net-(LED19-DO)") (class "Default")
      (node (ref "LED19") (pin "2-DOUT") (pinfunction "DO_2-DOUT") (pintype "output"))
      (node (ref "LED20") (pin "4-DIN") (pinfunction "DI_4-DIN") (pintype "input"))
    )
    (net (code "22") (name "Net-(LED20-DO)") (class "Default")
      (node (ref "LED20") (pin "2-DOUT") (pinfunction "DO_2-DOUT") (pintype "output"))
      (node (ref "LED21") (pin "4-DIN") (pinfunction "DI_4-DIN") (pintype "input"))
    )
    (net (code "23") (name "Net-(LED21-DO)") (class "Default")
      (node (ref "LED21") (pin "2-DOUT") (pinfunction "DO_2-DOUT") (pintype "output"))
      (node (ref "LED22") (pin "4-DIN") (pinfunction "DI_4-DIN") (pintype "input"))
    )
    (net (code "24") (name "Net-(LED22-DO)") (class "Default")
      (node (ref "LED22") (pin "2-DOUT") (pinfunction "DO_2-DOUT") (pintype "output"))
      (node (ref "LED23") (pin "4-DIN") (pinfunction "DI_4-DIN") (pintype "input"))
    )
    (net (code "25") (name "Net-(LED23-DO)") (class "Default")
      (node (ref "LED23") (pin "2-DOUT") (pinfunction "DO_2-DOUT") (pintype "output"))
      (node (ref "LED24") (pin "4-DIN") (pinfunction "DI_4-DIN") (pintype "input"))
    )
    (net (code "26") (name "Net-(LED24-DO)") (class "Default")
      (node (ref "LED24") (pin "2-DOUT") (pinfunction "DO_2-DOUT") (pintype "output"))
      (node (ref "LED25") (pin "4-DIN") (pinfunction "DI_4-DIN") (pintype "input"))
    )
    (net (code "27") (name "Net-(LED25-DO)") (class "Default")
      (node (ref "LED25") (pin "2-DOUT") (pinfunction "DO_2-DOUT") (pintype "output"))
      (node (ref "LED26") (pin "4-DIN") (pinfunction "DI_4-DIN") (pintype "input"))
    )
    (net (code "28") (name "Net-(LED26-DO)") (class "Default")
      (node (ref "LED26") (pin "2-DOUT") (pinfunction "DO_2-DOUT") (pintype "output"))
      (node (ref "LED27") (pin "4-DIN") (pinfunction "DI_4-DIN") (pintype "input"))
    )
    (net (code "29") (name "Net-(LED27-DO)") (class "Default")
      (node (ref "LED27") (pin "2-DOUT") (pinfunction "DO_2-DOUT") (pintype "output"))
      (node (ref "LED28") (pin "4-DIN") (pinfunction "DI_4-DIN") (pintype "input"))
    )
    (net (code "30") (name "Net-(LED28-DO)") (class "Default")
      (node (ref "LED28") (pin "2-DOUT") (pinfunction "DO_2-DOUT") (pintype "output"))
      (node (ref "LED29") (pin "4-DIN") (pinfunction "DI_4-DIN") (pintype "input"))
    )
    (net (code "31") (name "Net-(LED29-DO)") (class "Default")
      (node (ref "LED29") (pin "2-DOUT") (pinfunction "DO_2-DOUT") (pintype "output"))
      (node (ref "LED30") (pin "4-DIN") (pinfunction "DI_4-DIN") (pintype "input"))
    )
    (net (code "32") (name "Net-(LED31-DI)") (class "Default")
      (node (ref "LED31") (pin "4-DIN") (pinfunction "DI_4-DIN") (pintype "input"))
      (node (ref "LED50") (pin "2-DOUT") (pinfunction "DO_2-DOUT") (pintype "output"))
    )
    (net (code "33") (name "Net-(LED31-DO)") (class "Default")
      (node (ref "LED31") (pin "2-DOUT") (pinfunction "DO_2-DOUT") (pintype "output"))
      (node (ref "LED32") (pin "4-DIN") (pinfunction "DI_4-DIN") (pintype "input"))
    )
    (net (code "34") (name "Net-(LED32-DO)") (class "Default")
      (node (ref "LED32") (pin "2-DOUT") (pinfunction "DO_2-DOUT") (pintype "output"))
      (node (ref "LED33") (pin "4-DIN") (pinfunction "DI_4-DIN") (pintype "input"))
    )
    (net (code "35") (name "Net-(LED33-DO)") (class "Default")
      (node (ref "LED33") (pin "2-DOUT") (pinfunction "DO_2-DOUT") (pintype "output"))
      (node (ref "LED34") (pin "4-DIN") (pinfunction "DI_4-DIN") (pintype "input"))
    )
    (net (code "36") (name "Net-(LED34-DO)") (class "Default")
      (node (ref "LED34") (pin "2-DOUT") (pinfunction "DO_2-DOUT") (pintype "output"))
      (node (ref "LED35") (pin "4-DIN") (pinfunction "DI_4-DIN") (pintype "input"))
    )
    (net (code "37") (name "Net-(LED35-DO)") (class "Default")
      (node (ref "LED35") (pin "2-DOUT") (pinfunction "DO_2-DOUT") (pintype "output"))
      (node (ref "LED36") (pin "4-DIN") (pinfunction "DI_4-DIN") (pintype "input"))
    )
    (net (code "38") (name "Net-(LED36-DO)") (class "Default")
      (node (ref "LED36") (pin "2-DOUT") (pinfunction "DO_2-DOUT") (pintype "output"))
      (node (ref "LED37") (pin "4-DIN") (pinfunction "DI_4-DIN") (pintype "input"))
    )
    (net (code "39") (name "Net-(LED37-DO)") (class "Default")
      (node (ref "LED37") (pin "2-DOUT") (pinfunction "DO_2-DOUT") (pintype "output"))
      (node (ref "LED38") (pin "4-DIN") (pinfunction "DI_4-DIN") (pintype "input"))
    )
    (net (code "40") (name "Net-(LED38-DO)") (class "Default")
      (node (ref "LED38") (pin "2-DOUT") (pinfunction "DO_2-DOUT") (pintype "output"))
      (node (ref "LED39") (pin "4-DIN") (pinfunction "DI_4-DIN") (pintype "input"))
    )
    (net (code "41") (name "Net-(LED39-DO)") (class "Default")
      (node (ref "LED39") (pin "2-DOUT") (pinfunction "DO_2-DOUT") (pintype "output"))
      (node (ref "LED40") (pin "4-DIN") (pinfunction "DI_4-DIN") (pintype "input"))
    )
    (net (code "42") (name "Net-(LED40-DO)") (class "Default")
      (node (ref "LED40") (pin "2-DOUT") (pinfunction "DO_2-DOUT") (pintype "output"))
      (node (ref "LED41") (pin "4-DIN") (pinfunction "DI_4-DIN") (pintype "input"))
    )
    (net (code "43") (name "Net-(LED41-DO)") (class "Default")
      (node (ref "LED41") (pin "2-DOUT") (pinfunction "DO_2-DOUT") (pintype "output"))
      (node (ref "LED42") (pin "4-DIN") (pinfunction "DI_4-DIN") (pintype "input"))
    )
    (net (code "44") (name "Net-(LED43-DI)") (class "Default")
      (node (ref "LED43") (pin "4-DIN") (pinfunction "DI_4-DIN") (pintype "input"))
      (node (ref "LED56") (pin "2-DOUT") (pinfunction "DO_2-DOUT") (pintype "output"))
    )
    (net (code "45") (name "Net-(LED43-DO)") (class "Default")
      (node (ref "LED43") (pin "2-DOUT") (pinfunction "DO_2-DOUT") (pintype "output"))
      (node (ref "LED44") (pin "4-DIN") (pinfunction "DI_4-DIN") (pintype "input"))
    )
    (net (code "46") (name "Net-(LED44-DO)") (class "Default")
      (node (ref "LED44") (pin "2-DOUT") (pinfunction "DO_2-DOUT") (pintype "output"))
      (node (ref "LED45") (pin "4-DIN") (pinfunction "DI_4-DIN") (pintype "input"))
    )
    (net (code "47") (name "Net-(LED45-DO)") (class "Default")
      (node (ref "LED45") (pin "2-DOUT") (pinfunction "DO_2-DOUT") (pintype "output"))
      (node (ref "LED46") (pin "4-DIN") (pinfunction "DI_4-DIN") (pintype "input"))
    )
    (net (code "48") (name "Net-(LED46-DO)") (class "Default")
      (node (ref "LED46") (pin "2-DOUT") (pinfunction "DO_2-DOUT") (pintype "output"))
      (node (ref "LED47") (pin "4-DIN") (pinfunction "DI_4-DIN") (pintype "input"))
    )
    (net (code "49") (name "Net-(LED47-DO)") (class "Default")
      (node (ref "LED47") (pin "2-DOUT") (pinfunction "DO_2-DOUT") (pintype "output"))
      (node (ref "LED48") (pin "4-DIN") (pinfunction "DI_4-DIN") (pintype "input"))
    )
    (net (code "50") (name "Net-(LED48-DO)") (class "Default")
      (node (ref "LED48") (pin "2-DOUT") (pinfunction "DO_2-DOUT") (pintype "output"))
      (node (ref "LED49") (pin "4-DIN") (pinfunction "DI_4-DIN") (pintype "input"))
    )
    (net (code "51") (name "Net-(LED49-DO)") (class "Default")
      (node (ref "LED49") (pin "2-DOUT") (pinfunction "DO_2-DOUT") (pintype "output"))
      (node (ref "LED50") (pin "4-DIN") (pinfunction "DI_4-DIN") (pintype "input"))
    )
    (net (code "52") (name "Net-(LED51-DI)") (class "Default")
      (node (ref "LED51") (pin "4-DIN") (pinfunction "DI_4-DIN") (pintype "input"))
      (node (ref "LED60") (pin "2-DOUT") (pinfunction "DO_2-DOUT") (pintype "output"))
    )
    (net (code "53") (name "Net-(LED51-DO)") (class "Default")
      (node (ref "LED51") (pin "2-DOUT") (pinfunction "DO_2-DOUT") (pintype "output"))
      (node (ref "LED52") (pin "4-DIN") (pinfunction "DI_4-DIN") (pintype "input"))
    )
    (net (code "54") (name "Net-(LED52-DO)") (class "Default")
      (node (ref "LED52") (pin "2-DOUT") (pinfunction "DO_2-DOUT") (pintype "output"))
      (node (ref "LED53") (pin "4-DIN") (pinfunction "DI_4-DIN") (pintype "input"))
    )
    (net (code "55") (name "Net-(LED53-DO)") (class "Default")
      (node (ref "LED53") (pin "2-DOUT") (pinfunction "DO_2-DOUT") (pintype "output"))
      (node (ref "LED54") (pin "4-DIN") (pinfunction "DI_4-DIN") (pintype "input"))
    )
    (net (code "56") (name "Net-(LED54-DO)") (class "Default")
      (node (ref "LED54") (pin "2-DOUT") (pinfunction "DO_2-DOUT") (pintype "output"))
      (node (ref "LED55") (pin "4-DIN") (pinfunction "DI_4-DIN") (pintype "input"))
    )
    (net (code "57") (name "Net-(LED55-DO)") (class "Default")
      (node (ref "LED55") (pin "2-DOUT") (pinfunction "DO_2-DOUT") (pintype "output"))
      (node (ref "LED56") (pin "4-DIN") (pinfunction "DI_4-DIN") (pintype "input"))
    )
    (net (code "58") (name "Net-(LED57-DI)") (class "Default")
      (node (ref "LED57") (pin "4-DIN") (pinfunction "DI_4-DIN") (pintype "input"))
      (node (ref "LED61") (pin "2-DOUT") (pinfunction "DO_2-DOUT") (pintype "output"))
    )
    (net (code "59") (name "Net-(LED57-DO)") (class "Default")
      (node (ref "LED57") (pin "2-DOUT") (pinfunction "DO_2-DOUT") (pintype "output"))
      (node (ref "LED58") (pin "4-DIN") (pinfunction "DI_4-DIN") (pintype "input"))
    )
    (net (code "60") (name "Net-(LED58-DO)") (class "Default")
      (node (ref "LED58") (pin "2-DOUT") (pinfunction "DO_2-DOUT") (pintype "output"))
      (node (ref "LED59") (pin "4-DIN") (pinfunction "DI_4-DIN") (pintype "input"))
    )
    (net (code "61") (name "Net-(LED59-DO)") (class "Default")
      (node (ref "LED59") (pin "2-DOUT") (pinfunction "DO_2-DOUT") (pintype "output"))
      (node (ref "LED60") (pin "4-DIN") (pinfunction "DI_4-DIN") (pintype "input"))
    )
    (net (code "62") (name "VCC") (class "Default")
      (node (ref "C1") (pin "1") (pinfunction "1_1") (pintype "passive"))
      (node (ref "C10") (pin "1") (pinfunction "1_1") (pintype "passive"))
      (node (ref "C11") (pin "1") (pinfunction "1_1") (pintype "passive"))
      (node (ref "C12") (pin "1") (pinfunction "1_1") (pintype "passive"))
      (node (ref "C13") (pin "1") (pinfunction "1_1") (pintype "passive"))
      (node (ref "C14") (pin "1") (pinfunction "1_1") (pintype "passive"))
      (node (ref "C15") (pin "1") (pinfunction "1_1") (pintype "passive"))
      (node (ref "C16") (pin "1") (pinfunction "1_1") (pintype "passive"))
      (node (ref "C17") (pin "1") (pinfunction "1_1") (pintype "passive"))
      (node (ref "C18") (pin "1") (pinfunction "1_1") (pintype "passive"))
      (node (ref "C19") (pin "1") (pinfunction "1_1") (pintype "passive"))
      (node (ref "C2") (pin "1") (pinfunction "1_1") (pintype "passive"))
      (node (ref "C20") (pin "1") (pinfunction "1_1") (pintype "passive"))
      (node (ref "C21") (pin "1") (pinfunction "1_1") (pintype "passive"))
      (node (ref "C22") (pin "1") (pinfunction "1_1") (pintype "passive"))
      (node (ref "C23") (pin "1") (pinfunction "1_1") (pintype "passive"))
      (node (ref "C24") (pin "1") (pinfunction "1_1") (pintype "passive"))
      (node (ref "C25") (pin "1") (pinfunction "1_1") (pintype "passive"))
      (node (ref "C26") (pin "1") (pinfunction "1_1") (pintype "passive"))
      (node (ref "C27") (pin "1") (pinfunction "1_1") (pintype "passive"))
      (node (ref "C28") (pin "1") (pinfunction "1_1") (pintype "passive"))
      (node (ref "C29") (pin "1") (pinfunction "1_1") (pintype "passive"))
      (node (ref "C3") (pin "1") (pinfunction "1_1") (pintype "passive"))
      (node (ref "C30") (pin "1") (pinfunction "1_1") (pintype "passive"))
      (node (ref "C31") (pin "1") (pinfunction "1_1") (pintype "passive"))
      (node (ref "C32") (pin "1") (pinfunction "1_1") (pintype "passive"))
      (node (ref "C33") (pin "1") (pinfunction "1_1") (pintype "passive"))
      (node (ref "C34") (pin "1") (pinfunction "1_1") (pintype "passive"))
      (node (ref "C35") (pin "1") (pinfunction "1_1") (pintype "passive"))
      (node (ref "C36") (pin "1") (pinfunction "1_1") (pintype "passive"))
      (node (ref "C37") (pin "1") (pinfunction "1_1") (pintype "passive"))
      (node (ref "C38") (pin "1") (pinfunction "1_1") (pintype "passive"))
      (node (ref "C39") (pin "1") (pinfunction "1_1") (pintype "passive"))
      (node (ref "C4") (pin "1") (pinfunction "1_1") (pintype "passive"))
      (node (ref "C40") (pin "1") (pinfunction "1_1") (pintype "passive"))
      (node (ref "C41") (pin "1") (pinfunction "1_1") (pintype "passive"))
      (node (ref "C42") (pin "1") (pinfunction "1_1") (pintype "passive"))
      (node (ref "C43") (pin "1") (pinfunction "1_1") (pintype "passive"))
      (node (ref "C44") (pin "1") (pinfunction "1_1") (pintype "passive"))
      (node (ref "C45") (pin "1") (pinfunction "1_1") (pintype "passive"))
      (node (ref "C46") (pin "1") (pinfunction "1_1") (pintype "passive"))
      (node (ref "C47") (pin "1") (pinfunction "1_1") (pintype "passive"))
      (node (ref "C48") (pin "1") (pinfunction "1_1") (pintype "passive"))
      (node (ref "C49") (pin "1") (pinfunction "1_1") (pintype "passive"))
      (node (ref "C5") (pin "1") (pinfunction "1_1") (pintype "passive"))
      (node (ref "C50") (pin "1") (pinfunction "1_1") (pintype "passive"))
      (node (ref "C51") (pin "1") (pinfunction "1_1") (pintype "passive"))
      (node (ref "C52") (pin "1") (pinfunction "1_1") (pintype "passive"))
      (node (ref "C53") (pin "1") (pinfunction "1_1") (pintype "passive"))
      (node (ref "C54") (pin "1") (pinfunction "1_1") (pintype "passive"))
      (node (ref "C55") (pin "1") (pinfunction "1_1") (pintype "passive"))
      (node (ref "C56") (pin "1") (pinfunction "1_1") (pintype "passive"))
      (node (ref "C57") (pin "1") (pinfunction "1_1") (pintype "passive"))
      (node (ref "C58") (pin "1") (pinfunction "1_1") (pintype "passive"))
      (node (ref "C59") (pin "1") (pinfunction "1_1") (pintype "passive"))
      (node (ref "C6") (pin "1") (pinfunction "1_1") (pintype "passive"))
      (node (ref "C60") (pin "1") (pinfunction "1_1") (pintype "passive"))
      (node (ref "C61") (pin "1") (pinfunction "1_1") (pintype "passive"))
      (node (ref "C7") (pin "1") (pinfunction "1_1") (pintype "passive"))
      (node (ref "C8") (pin "1") (pinfunction "1_1") (pintype "passive"))
      (node (ref "C9") (pin "1") (pinfunction "1_1") (pintype "passive"))
      (node (ref "LED1") (pin "1-VDD") (pinfunction "VDD_1-VDD") (pintype "power_in"))
      (node (ref "LED10") (pin "1-VDD") (pinfunction "VDD_1-VDD") (pintype "power_in"))
      (node (ref "LED11") (pin "1-VDD") (pinfunction "VDD_1-VDD") (pintype "power_in"))
      (node (ref "LED12") (pin "1-VDD") (pinfunction "VDD_1-VDD") (pintype "power_in"))
      (node (ref "LED13") (pin "1-VDD") (pinfunction "VDD_1-VDD") (pintype "power_in"))
      (node (ref "LED14") (pin "1-VDD") (pinfunction "VDD_1-VDD") (pintype "power_in"))
      (node (ref "LED15") (pin "1-VDD") (pinfunction "VDD_1-VDD") (pintype "power_in"))
      (node (ref "LED16") (pin "1-VDD") (pinfunction "VDD_1-VDD") (pintype "power_in"))
      (node (ref "LED17") (pin "1-VDD") (pinfunction "VDD_1-VDD") (pintype "power_in"))
      (node (ref "LED18") (pin "1-VDD") (pinfunction "VDD_1-VDD") (pintype "power_in"))
      (node (ref "LED19") (pin "1-VDD") (pinfunction "VDD_1-VDD") (pintype "power_in"))
      (node (ref "LED2") (pin "1-VDD") (pinfunction "VDD_1-VDD") (pintype "power_in"))
      (node (ref "LED20") (pin "1-VDD") (pinfunction "VDD_1-VDD") (pintype "power_in"))
      (node (ref "LED21") (pin "1-VDD") (pinfunction "VDD_1-VDD") (pintype "power_in"))
      (node (ref "LED22") (pin "1-VDD") (pinfunction "VDD_1-VDD") (pintype "power_in"))
      (node (ref "LED23") (pin "1-VDD") (pinfunction "VDD_1-VDD") (pintype "power_in"))
      (node (ref "LED24") (pin "1-VDD") (pinfunction "VDD_1-VDD") (pintype "power_in"))
      (node (ref "LED25") (pin "1-VDD") (pinfunction "VDD_1-VDD") (pintype "power_in"))
      (node (ref "LED26") (pin "1-VDD") (pinfunction "VDD_1-VDD") (pintype "power_in"))
      (node (ref "LED27") (pin "1-VDD") (pinfunction "VDD_1-VDD") (pintype "power_in"))
      (node (ref "LED28") (pin "1-VDD") (pinfunction "VDD_1-VDD") (pintype "power_in"))
      (node (ref "LED29") (pin "1-VDD") (pinfunction "VDD_1-VDD") (pintype "power_in"))
      (node (ref "LED3") (pin "1-VDD") (pinfunction "VDD_1-VDD") (pintype "power_in"))
      (node (ref "LED30") (pin "1-VDD") (pinfunction "VDD_1-VDD") (pintype "power_in"))
      (node (ref "LED31") (pin "1-VDD") (pinfunction "VDD_1-VDD") (pintype "power_in"))
      (node (ref "LED32") (pin "1-VDD") (pinfunction "VDD_1-VDD") (pintype "power_in"))
      (node (ref "LED33") (pin "1-VDD") (pinfunction "VDD_1-VDD") (pintype "power_in"))
      (node (ref "LED34") (pin "1-VDD") (pinfunction "VDD_1-VDD") (pintype "power_in"))
      (node (ref "LED35") (pin "1-VDD") (pinfunction "VDD_1-VDD") (pintype "power_in"))
      (node (ref "LED36") (pin "1-VDD") (pinfunction "VDD_1-VDD") (pintype "power_in"))
      (node (ref "LED37") (pin "1-VDD") (pinfunction "VDD_1-VDD") (pintype "power_in"))
      (node (ref "LED38") (pin "1-VDD") (pinfunction "VDD_1-VDD") (pintype "power_in"))
      (node (ref "LED39") (pin "1-VDD") (pinfunction "VDD_1-VDD") (pintype "power_in"))
      (node (ref "LED4") (pin "1-VDD") (pinfunction "VDD_1-VDD") (pintype "power_in"))
      (node (ref "LED40") (pin "1-VDD") (pinfunction "VDD_1-VDD") (pintype "power_in"))
      (node (ref "LED41") (pin "1-VDD") (pinfunction "VDD_1-VDD") (pintype "power_in"))
      (node (ref "LED42") (pin "1-VDD") (pinfunction "VDD_1-VDD") (pintype "power_in"))
      (node (ref "LED43") (pin "1-VDD") (pinfunction "VDD_1-VDD") (pintype "power_in"))
      (node (ref "LED44") (pin "1-VDD") (pinfunction "VDD_1-VDD") (pintype "power_in"))
      (node (ref "LED45") (pin "1-VDD") (pinfunction "VDD_1-VDD") (pintype "power_in"))
      (node (ref "LED46") (pin "1-VDD") (pinfunction "VDD_1-VDD") (pintype "power_in"))
      (node (ref "LED47") (pin "1-VDD") (pinfunction "VDD_1-VDD") (pintype "power_in"))
      (node (ref "LED48") (pin "1-VDD") (pinfunction "VDD_1-VDD") (pintype "power_in"))
      (node (ref "LED49") (pin "1-VDD") (pinfunction "VDD_1-VDD") (pintype "power_in"))
      (node (ref "LED5") (pin "1-VDD") (pinfunction "VDD_1-VDD") (pintype "power_in"))
      (node (ref "LED50") (pin "1-VDD") (pinfunction "VDD_1-VDD") (pintype "power_in"))
      (node (ref "LED51") (pin "1-VDD") (pinfunction "VDD_1-VDD") (pintype "power_in"))
      (node (ref "LED52") (pin "1-VDD") (pinfunction "VDD_1-VDD") (pintype "power_in"))
      (node (ref "LED53") (pin "1-VDD") (pinfunction "VDD_1-VDD") (pintype "power_in"))
      (node (ref "LED54") (pin "1-VDD") (pinfunction "VDD_1-VDD") (pintype "power_in"))
      (node (ref "LED55") (pin "1-VDD") (pinfunction "VDD_1-VDD") (pintype "power_in"))
      (node (ref "LED56") (pin "1-VDD") (pinfunction "VDD_1-VDD") (pintype "power_in"))
      (node (ref "LED57") (pin "1-VDD") (pinfunction "VDD_1-VDD") (pintype "power_in"))
      (node (ref "LED58") (pin "1-VDD") (pinfunction "VDD_1-VDD") (pintype "power_in"))
      (node (ref "LED59") (pin "1-VDD") (pinfunction "VDD_1-VDD") (pintype "power_in"))
      (node (ref "LED6") (pin "1-VDD") (pinfunction "VDD_1-VDD") (pintype "power_in"))
      (node (ref "LED60") (pin "1-VDD") (pinfunction "VDD_1-VDD") (pintype "power_in"))
      (node (ref "LED61") (pin "1-VDD") (pinfunction "VDD_1-VDD") (pintype "power_in"))
      (node (ref "LED7") (pin "1-VDD") (pinfunction "VDD_1-VDD") (pintype "power_in"))
      (node (ref "LED8") (pin "1-VDD") (pinfunction "VDD_1-VDD") (pintype "power_in"))
      (node (ref "LED9") (pin "1-VDD") (pinfunction "VDD_1-VDD") (pintype "power_in"))
    )
    (net (code "63") (name "unconnected-(LED16-DO-Pad2-DOUT)") (class "Default")
      (node (ref "LED16") (pin "2-DOUT") (pinfunction "DO_2-DOUT") (pintype "output"))
    )
    (net (code "64") (name "unconnected-(LED61-DI-Pad4-DIN)") (class "Default")
      (node (ref "LED61") (pin "4-DIN") (pinfunction "DI_4-DIN") (pintype "input"))
    )
  )
)
